# NG6013.net
KiCad netlist of a schematic drawn in Altium Designer
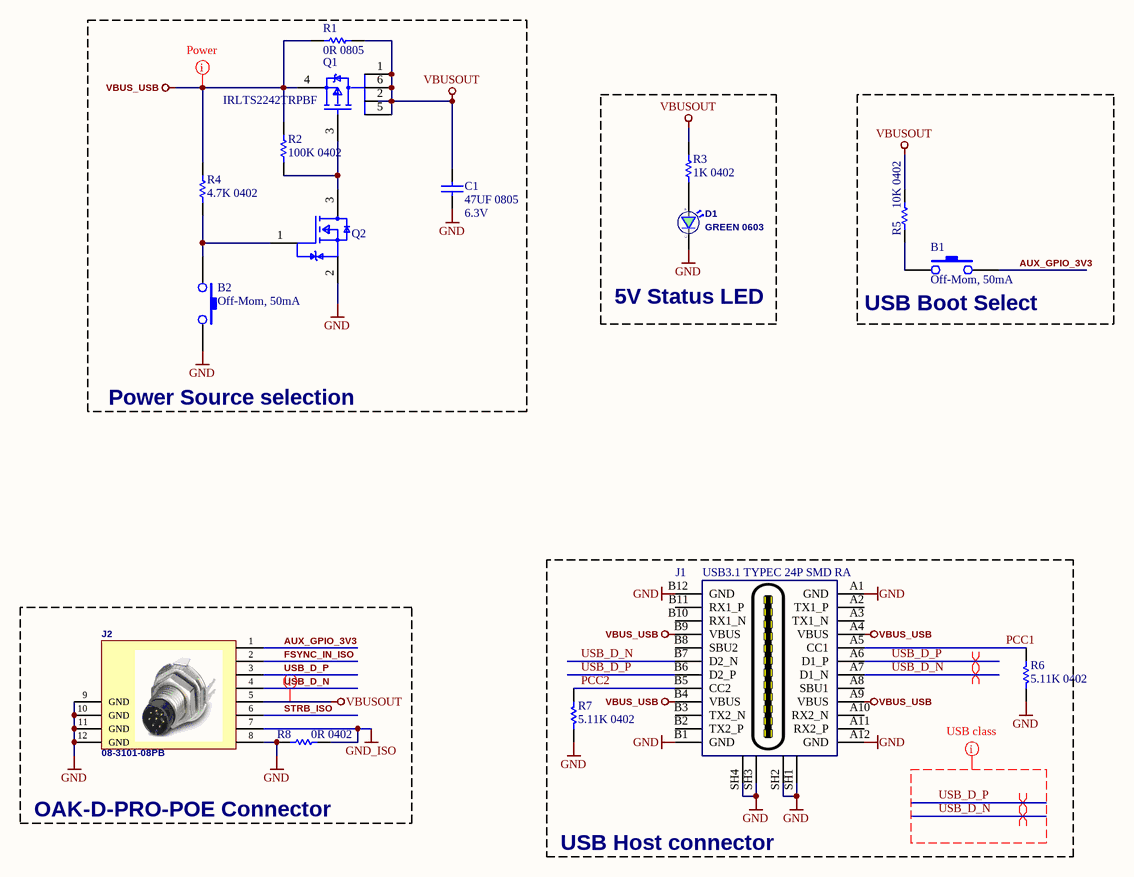
[diagram p0: NG6013.SchDoc]

(export (version "E")
  (design (tool "Eeschema 10.0.6"))
  (components
    (comp (ref "B1")
      (value "Off-Mom, 50mA")
      (footprint "LuxonisMaster:DTSM-32N-V")
      (description "SWITCH TACTILE SMT 3.5mm * 6mm , brown 160gf")
      (libsource (lib "LuxonisMaster") (part "DTSM-32N-V"))
    )
    (comp (ref "B2")
      (value "Off-Mom, 50mA")
      (footprint "LuxonisMaster:DTSM-32N-V")
      (description "SWITCH TACTILE SMT 3.5mm * 6mm , brown 160gf")
      (libsource (lib "LuxonisMaster") (part "DTSM-32N-V"))
    )
    (comp (ref "C1")
      (value "47UF 0805")
      (footprint "CAP_Altium_Vault_Generic:CAPC0805(2012)145_L")
      (description "CAP CER 47UF 6.3V X5R 0805")
      (fields (field (name "TOLERANCE") "20%") (field (name "VOLTAGE") "6.3V"))
      (libsource (lib "LuxonisMaster") (part "GRM21BR60J476ME15L"))
    )
    (comp (ref "D1")
      (value "GREEN 0603")
      (footprint "LuxonisMaster:SML_D1xx8W")
      (description "LED GREEN DIFFUSED 0603 SMD Green 572nm LED Indication - Discrete 2.2V 0603 (1608 Metric)")
      (fields (field (name "MANUFACTURER") "Rohm") (field (name "MANUFACTURER PART NUMBER") "SML-D12M8WT86"))
      (libsource (lib "LuxonisMaster") (part "SML-D12M8WT86"))
    )
    (comp (ref "J1")
      (value "USB3.1 TYPEC 24P SMD RA")
      (footprint "LuxonisMaster:105450-0101")
      (description "CONN RCP USB3.1 TYPEC 24P SMD RA")
      (libsource (lib "LuxonisMaster") (part "105450-0101"))
    )
    (comp (ref "J2")
      (value "08-3101-08PB")
      (footprint "1424236")
      (description "Circular Connector")
      (libsource (lib "NG6012_R0M0E0") (part "1424236"))
    )
    (comp (ref "Q1")
      (value "IRLTS2242TRPBF")
      (footprint "TSOP-6-MFG")
      (description "MOSFET P-CH 20V 6.9A 6TSOP")
      (libsource (lib "DM6010_R0M0E0") (part "IRLTS2242TRPBF"))
    )
    (comp (ref "Q2")
      (value "RE1C002UNTCL")
      (footprint "LuxonisMaster:RE1C002UNTCL")
      (description "VISHAY - SI1062X-T1-GE3 - MOSFET Transistor, N Channel, 530 mA, 20 V, 0.35 ohm, 4.5 V, 1 V")
      (libsource (lib "LuxonisMaster") (part "RE1C002UNTCL"))
    )
    (comp (ref "R1")
      (value "0R 0805")
      (footprint "RESC0805(2012)_L")
      (description "RES SMD 0.0R OHM 1% 1/8W 0805")
      (libsource (lib "LuxonisMaster") (part "CRCW08050000Z0EA"))
    )
    (comp (ref "R2")
      (value "100K 0402")
      (footprint "RES_Altium_Vault_Generic:RESC0402(1005)_L")
      (description "RES SMD 100K OHM 1% 1/16W 0402")
      (fields (field (name "TOLERANCE") "1%"))
      (libsource (lib "LuxonisMaster") (part "RC0402FR-07100KL"))
    )
    (comp (ref "R3")
      (value "1K 0402")
      (footprint "RES_Altium_Vault_Generic:RESC0402(1005)_L")
      (fields (field (name "TOLERANCE") "1%"))
      (libsource (lib "LuxonisMaster") (part "RC0402FR-071KL"))
    )
    (comp (ref "R4")
      (value "4.7K 0402")
      (footprint "RES_Altium_Vault_Generic:RESC0402(1005)_N")
      (description "RES SMD 4.7K OHM 1% 1/16W 0402")
      (fields (field (name "TOLERANCE") "1%"))
      (libsource (lib "LuxonisMaster") (part "RC0402FR-074K7L"))
    )
    (comp (ref "R5")
      (value "10K 0402")
      (footprint "RES_Altium_Vault_Generic:RESC0402(1005)_L")
      (fields (field (name "TOLERANCE") "1%"))
      (libsource (lib "LuxonisMaster") (part "RC0402FR-1310KL"))
    )
    (comp (ref "R6")
      (value "5.11K 0402")
      (footprint "RES_Altium_Vault_Generic:RESC0402(1005)_L")
      (fields (field (name "TOLERANCE") "1%"))
      (libsource (lib "LuxonisMaster") (part "RC0402FR-075K11L"))
    )
    (comp (ref "R7")
      (value "5.11K 0402")
      (footprint "RES_Altium_Vault_Generic:RESC0402(1005)_L")
      (fields (field (name "TOLERANCE") "1%"))
      (libsource (lib "LuxonisMaster") (part "RC0402FR-075K11L"))
    )
    (comp (ref "R8")
      (value "0R 0402")
      (footprint "RES_Altium_Vault_Generic:RESC0402(1005)_L")
      (description "RES SMD 0 OHM JUMPER 1/16W 0402")
      (fields (field (name "TOLERANCE") "5%"))
      (libsource (lib "LuxonisMaster") (part "CRCW04020000Z0ED"))
    )
  )
  (nets
    (net (code "1") (name "/AUX_GPIO_3V3") (class "Default")
      (node (ref "B1") (pin "1") (pinfunction "1_1") (pintype "passive"))
      (node (ref "J2") (pin "1") (pinfunction "1_1") (pintype "passive"))
    )
    (net (code "2") (name "/FSYNC_IN_ISO") (class "Default")
      (node (ref "J2") (pin "2") (pinfunction "2_2") (pintype "passive"))
    )
    (net (code "3") (name "/PCC1") (class "Default")
      (node (ref "J1") (pin "A5") (pinfunction "CC1_A5") (pintype "passive"))
      (node (ref "R6") (pin "2") (pinfunction "2_2") (pintype "passive"))
    )
    (net (code "4") (name "/PCC2") (class "Default")
      (node (ref "J1") (pin "B5") (pinfunction "CC2_B5") (pintype "passive"))
      (node (ref "R7") (pin "2") (pinfunction "2_2") (pintype "passive"))
    )
    (net (code "5") (name "/STRB_ISO") (class "Default")
      (node (ref "J2") (pin "6") (pinfunction "6_6") (pintype "passive"))
    )
    (net (code "6") (name "/USB_D_N") (class "Default")
      (node (ref "J1") (pin "A7") (pinfunction "D1_N_A7") (pintype "passive"))
      (node (ref "J1") (pin "B7") (pinfunction "D2_N_B7") (pintype "passive"))
      (node (ref "J2") (pin "4") (pinfunction "4_4") (pintype "passive"))
    )
    (net (code "7") (name "/USB_D_P") (class "Default")
      (node (ref "J1") (pin "A6") (pinfunction "D1_P_A6") (pintype "passive"))
      (node (ref "J1") (pin "B6") (pinfunction "D2_P_B6") (pintype "passive"))
      (node (ref "J2") (pin "3") (pinfunction "3_3") (pintype "passive"))
    )
    (net (code "8") (name "GND") (class "Default")
      (node (ref "B2") (pin "1") (pinfunction "1_1") (pintype "passive"))
      (node (ref "C1") (pin "1") (pinfunction "1_1") (pintype "passive"))
      (node (ref "D1") (pin "1") (pinfunction "C_1") (pintype "passive"))
      (node (ref "J1") (pin "A1") (pinfunction "GND_A1") (pintype "passive"))
      (node (ref "J1") (pin "A12") (pinfunction "GND_A12") (pintype "passive"))
      (node (ref "J1") (pin "B1") (pinfunction "GND_B1") (pintype "passive"))
      (node (ref "J1") (pin "B12") (pinfunction "GND_B12") (pintype "passive"))
      (node (ref "J1") (pin "SH1") (pinfunction "SH_SH1") (pintype "passive"))
      (node (ref "J1") (pin "SH2") (pinfunction "SH_SH2") (pintype "passive"))
      (node (ref "J1") (pin "SH3") (pinfunction "SH_SH3") (pintype "passive"))
      (node (ref "J1") (pin "SH4") (pinfunction "SH_SH4") (pintype "passive"))
      (node (ref "J2") (pin "10") (pinfunction "GND_10") (pintype "passive"))
      (node (ref "J2") (pin "11") (pinfunction "GND_11") (pintype "passive"))
      (node (ref "J2") (pin "12") (pinfunction "GND_12") (pintype "passive"))
      (node (ref "J2") (pin "8") (pinfunction "8_8") (pintype "passive"))
      (node (ref "J2") (pin "9") (pinfunction "GND_9") (pintype "passive"))
      (node (ref "Q2") (pin "2") (pinfunction "Source_2") (pintype "passive"))
      (node (ref "R6") (pin "1") (pinfunction "1_1") (pintype "passive"))
      (node (ref "R7") (pin "1") (pinfunction "1_1") (pintype "passive"))
      (node (ref "R8") (pin "1") (pinfunction "1_1") (pintype "passive"))
    )
    (net (code "9") (name "GND_ISO") (class "Default")
      (node (ref "J2") (pin "7") (pinfunction "7_7") (pintype "passive"))
      (node (ref "R8") (pin "2") (pinfunction "2_2") (pintype "passive"))
    )
    (net (code "10") (name "Net-(B1-Pad2)") (class "Default")
      (node (ref "B1") (pin "2") (pinfunction "2_2") (pintype "passive"))
      (node (ref "R5") (pin "1") (pinfunction "1_1") (pintype "passive"))
    )
    (net (code "11") (name "Net-(D1-A)") (class "Default")
      (node (ref "D1") (pin "2") (pinfunction "A_2") (pintype "passive"))
      (node (ref "R3") (pin "1") (pinfunction "1_1") (pintype "passive"))
    )
    (net (code "12") (name "Net-(Q1-G)") (class "Default")
      (node (ref "Q1") (pin "3") (pinfunction "G_3") (pintype "passive"))
      (node (ref "Q2") (pin "3") (pinfunction "Drain_3") (pintype "passive"))
      (node (ref "R2") (pin "1") (pinfunction "1_1") (pintype "passive"))
    )
    (net (code "13") (name "Net-(Q2-Gate)") (class "Default")
      (node (ref "B2") (pin "2") (pinfunction "2_2") (pintype "passive"))
      (node (ref "Q2") (pin "1") (pinfunction "Gate_1") (pintype "passive"))
      (node (ref "R4") (pin "1") (pinfunction "1_1") (pintype "passive"))
    )
    (net (code "14") (name "VBUSOUT") (class "Default")
      (node (ref "C1") (pin "2") (pinfunction "2_2") (pintype "passive"))
      (node (ref "J2") (pin "5") (pinfunction "5_5") (pintype "passive"))
      (node (ref "Q1") (pin "1") (pinfunction "D_1") (pintype "passive"))
      (node (ref "Q1") (pin "2") (pinfunction "D_2") (pintype "passive"))
      (node (ref "Q1") (pin "5") (pinfunction "D_5") (pintype "passive"))
      (node (ref "Q1") (pin "6") (pinfunction "D_6") (pintype "passive"))
      (node (ref "R1") (pin "2") (pinfunction "2_2") (pintype "passive"))
      (node (ref "R3") (pin "2") (pinfunction "2_2") (pintype "passive"))
      (node (ref "R5") (pin "2") (pinfunction "2_2") (pintype "passive"))
    )
    (net (code "15") (name "VBUS_USB") (class "Default")
      (node (ref "J1") (pin "A4") (pinfunction "VBUS_A4") (pintype "passive"))
      (node (ref "J1") (pin "A9") (pinfunction "VBUS_A9") (pintype "passive"))
      (node (ref "J1") (pin "B4") (pinfunction "VBUS_B4") (pintype "passive"))
      (node (ref "J1") (pin "B9") (pinfunction "VBUS_B9") (pintype "passive"))
      (node (ref "Q1") (pin "4") (pinfunction "S_4") (pintype "passive"))
      (node (ref "R1") (pin "1") (pinfunction "1_1") (pintype "passive"))
      (node (ref "R2") (pin "2") (pinfunction "2_2") (pintype "passive"))
      (node (ref "R4") (pin "2") (pinfunction "2_2") (pintype "passive"))
    )
    (net (code "16") (name "unconnected-(J1-RX1_N-PadB10)") (class "Default")
      (node (ref "J1") (pin "B10") (pinfunction "RX1_N_B10") (pintype "passive"))
    )
    (net (code "17") (name "unconnected-(J1-RX1_P-PadB11)") (class "Default")
      (node (ref "J1") (pin "B11") (pinfunction "RX1_P_B11") (pintype "passive"))
    )
    (net (code "18") (name "unconnected-(J1-RX2_N-PadA10)") (class "Default")
      (node (ref "J1") (pin "A10") (pinfunction "RX2_N_A10") (pintype "passive"))
    )
    (net (code "19") (name "unconnected-(J1-RX2_P-PadA11)") (class "Default")
      (node (ref "J1") (pin "A11") (pinfunction "RX2_P_A11") (pintype "passive"))
    )
    (net (code "20") (name "unconnected-(J1-SBU1-PadA8)") (class "Default")
      (node (ref "J1") (pin "A8") (pinfunction "SBU1_A8") (pintype "passive"))
    )
    (net (code "21") (name "unconnected-(J1-SBU2-PadB8)") (class "Default")
      (node (ref "J1") (pin "B8") (pinfunction "SBU2_B8") (pintype "passive"))
    )
    (net (code "22") (name "unconnected-(J1-TX1_N-PadA3)") (class "Default")
      (node (ref "J1") (pin "A3") (pinfunction "TX1_N_A3") (pintype "passive"))
    )
    (net (code "23") (name "unconnected-(J1-TX1_P-PadA2)") (class "Default")
      (node (ref "J1") (pin "A2") (pinfunction "TX1_P_A2") (pintype "passive"))
    )
    (net (code "24") (name "unconnected-(J1-TX2_N-PadB3)") (class "Default")
      (node (ref "J1") (pin "B3") (pinfunction "TX2_N_B3") (pintype "passive"))
    )
    (net (code "25") (name "unconnected-(J1-TX2_P-PadB2)") (class "Default")
      (node (ref "J1") (pin "B2") (pinfunction "TX2_P_B2") (pintype "passive"))
    )
  )
)
